# FGPMMOPA6x.net
KiCad netlist of a schematic drawn in EAGLE
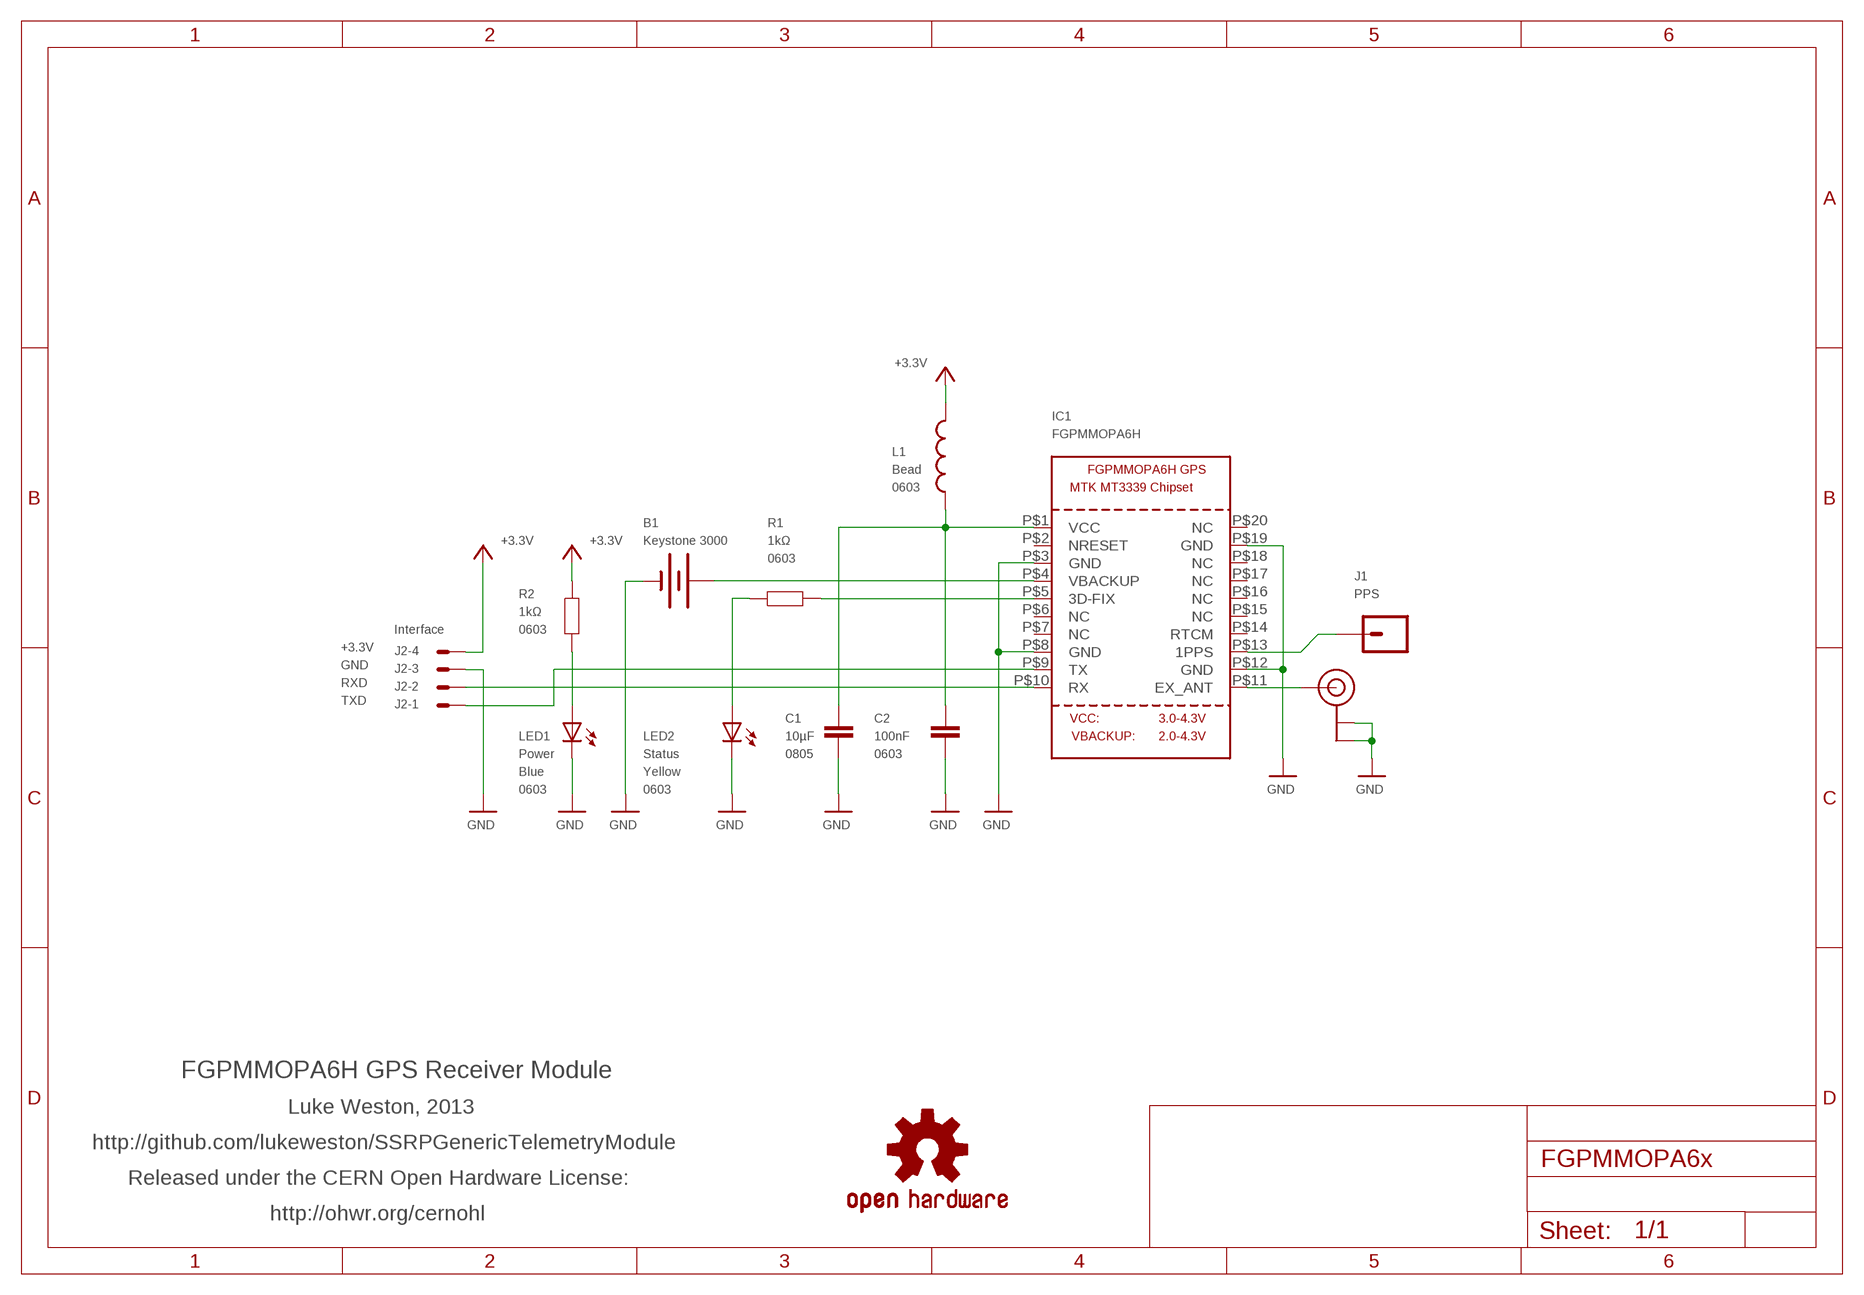
[diagram p0: schematic, sheet 1]

(export (version "E")
  (design (tool "Eeschema 10.0.6"))
  (components
    (comp (ref "B1")
      (value "Keystone 3000")
      (footprint "eagle-import:BATTCON_12MM")
      (libsource (lib "eagle-import") (part "BATTERY12MM"))
    )
    (comp (ref "C1")
      (value "10µF")
      (footprint "eagle-import:0805")
      (fields (field (name "PACKAGE") "0805"))
      (libsource (lib "eagle-import") (part "CAP0805"))
    )
    (comp (ref "C2")
      (value "100nF")
      (footprint "eagle-import:0603")
      (fields (field (name "PACKAGE") "0603"))
      (libsource (lib "eagle-import") (part "CAP0603"))
    )
    (comp (ref "IC1")
      (value "FGPMMOPA6H")
      (footprint "eagle-import:FGPMMOPA6H")
      (libsource (lib "eagle-import") (part "GPS_FGPMMOPA6H"))
    )
    (comp (ref "J1")
      (value "PPS")
      (footprint "eagle-import:1X01")
      (libsource (lib "eagle-import") (part "M01PTH"))
    )
    (comp (ref "J2")
      (value "Interface")
      (footprint "eagle-import:22-23-2041")
      (fields (field (name "MF") "MOLEX") (field (name "MPN") "22-23-2041"))
      (libsource (lib "eagle-import") (part "22-23-2041"))
    )
    (comp (ref "J3")
      (value "U.FL")
      (footprint "eagle-import:U.FL")
      (libsource (lib "eagle-import") (part "U.FL"))
    )
    (comp (ref "L1")
      (value "Bead")
      (footprint "eagle-import:0603")
      (fields (field (name "PACKAGE") "0603"))
      (libsource (lib "eagle-import") (part "INDUCTOR0603"))
    )
    (comp (ref "LED1")
      (value "Power")
      (footprint "eagle-import:LED-0603")
      (fields (field (name "COLOUR") "Blue") (field (name "PACKAGE") "0603"))
      (libsource (lib "eagle-import") (part "LED0603"))
    )
    (comp (ref "LED2")
      (value "Status")
      (footprint "eagle-import:LED-0603")
      (fields (field (name "COLOUR") "Yellow") (field (name "PACKAGE") "0603"))
      (libsource (lib "eagle-import") (part "LED0603"))
    )
    (comp (ref "R1")
      (value "1kΩ")
      (footprint "eagle-import:0603")
      (fields (field (name "PACKAGE") "0603"))
      (libsource (lib "eagle-import") (part "RESISTOR0603"))
    )
    (comp (ref "R2")
      (value "1kΩ")
      (footprint "eagle-import:0603")
      (fields (field (name "PACKAGE") "0603"))
      (libsource (lib "eagle-import") (part "RESISTOR0603"))
    )
    (comp (ref "SY")
      (value "OSHW-LOGOS")
      (footprint "eagle-import:OSHW-LOGO-S")
      (libsource (lib "eagle-import") (part "OSHW-LOGOS"))
    )
  )
  (nets
    (net (code "1") (name "+3.3V") (class "Default")
      (node (ref "J2") (pin "4") (pinfunction "S_4") (pintype "passive"))
      (node (ref "L1") (pin "2") (pinfunction "2_2") (pintype "passive"))
      (node (ref "R2") (pin "2") (pinfunction "2_2") (pintype "passive"))
    )
    (net (code "2") (name "GND") (class "Default")
      (node (ref "B1") (pin "GND") (pinfunction "-_GND") (pintype "power_in"))
      (node (ref "C1") (pin "1") (pinfunction "1_1") (pintype "passive"))
      (node (ref "C2") (pin "1") (pinfunction "1_1") (pintype "passive"))
      (node (ref "IC1") (pin "P$12") (pinfunction "GND_P$12") (pintype "bidirectional"))
      (node (ref "IC1") (pin "P$19") (pinfunction "GND_P$19") (pintype "bidirectional"))
      (node (ref "IC1") (pin "P$3") (pinfunction "GND_P$3") (pintype "bidirectional"))
      (node (ref "IC1") (pin "P$8") (pinfunction "GND_P$8") (pintype "bidirectional"))
      (node (ref "J2") (pin "3") (pinfunction "S_3") (pintype "passive"))
      (node (ref "J3") (pin "P$1") (pinfunction "GND_P$1") (pintype "bidirectional"))
      (node (ref "J3") (pin "P$2") (pinfunction "GND_P$2") (pintype "bidirectional"))
      (node (ref "LED1") (pin "C") (pinfunction "C_C") (pintype "passive"))
      (node (ref "LED2") (pin "C") (pinfunction "C_C") (pintype "passive"))
    )
    (net (code "3") (name "Net-(B1-+)") (class "Default")
      (node (ref "B1") (pin "PWR@1") (pinfunction "+_PWR@1") (pintype "power_in"))
      (node (ref "IC1") (pin "P$4") (pinfunction "VBACKUP_P$4") (pintype "bidirectional"))
    )
    (net (code "4") (name "Net-(IC1-1PPS)") (class "Default")
      (node (ref "IC1") (pin "P$13") (pinfunction "1PPS_P$13") (pintype "bidirectional"))
      (node (ref "J1") (pin "1") (pinfunction "1_1") (pintype "passive"))
    )
    (net (code "5") (name "Net-(IC1-3D-FIX)") (class "Default")
      (node (ref "IC1") (pin "P$5") (pinfunction "3D-FIX_P$5") (pintype "bidirectional"))
      (node (ref "R1") (pin "2") (pinfunction "2_2") (pintype "passive"))
    )
    (net (code "6") (name "Net-(IC1-EX_ANT)") (class "Default")
      (node (ref "IC1") (pin "P$11") (pinfunction "EX_ANT_P$11") (pintype "bidirectional"))
      (node (ref "J3") (pin "P$3") (pinfunction "SIGNAL_P$3") (pintype "bidirectional"))
    )
    (net (code "7") (name "Net-(IC1-RX)") (class "Default")
      (node (ref "IC1") (pin "P$10") (pinfunction "RX_P$10") (pintype "bidirectional"))
      (node (ref "J2") (pin "2") (pinfunction "S_2") (pintype "passive"))
    )
    (net (code "8") (name "Net-(IC1-TX)") (class "Default")
      (node (ref "IC1") (pin "P$9") (pinfunction "TX_P$9") (pintype "bidirectional"))
      (node (ref "J2") (pin "1") (pinfunction "S_1") (pintype "passive"))
    )
    (net (code "9") (name "Net-(IC1-VCC)") (class "Default")
      (node (ref "C1") (pin "2") (pinfunction "2_2") (pintype "passive"))
      (node (ref "C2") (pin "2") (pinfunction "2_2") (pintype "passive"))
      (node (ref "IC1") (pin "P$1") (pinfunction "VCC_P$1") (pintype "bidirectional"))
      (node (ref "L1") (pin "1") (pinfunction "1_1") (pintype "passive"))
    )
    (net (code "10") (name "Net-(LED1-PadA)") (class "Default")
      (node (ref "LED1") (pin "A") (pinfunction "A_A") (pintype "passive"))
      (node (ref "R2") (pin "1") (pinfunction "1_1") (pintype "passive"))
    )
    (net (code "11") (name "Net-(LED2-PadA)") (class "Default")
      (node (ref "LED2") (pin "A") (pinfunction "A_A") (pintype "passive"))
      (node (ref "R1") (pin "1") (pinfunction "1_1") (pintype "passive"))
    )
    (net (code "12") (name "unconnected-(IC1-NC-PadP$6)") (class "Default")
      (node (ref "IC1") (pin "P$6") (pinfunction "NC_P$6") (pintype "bidirectional"))
    )
    (net (code "13") (name "unconnected-(IC1-NC-PadP$7)") (class "Default")
      (node (ref "IC1") (pin "P$7") (pinfunction "NC_P$7") (pintype "bidirectional"))
    )
    (net (code "14") (name "unconnected-(IC1-NC-PadP$15)") (class "Default")
      (node (ref "IC1") (pin "P$15") (pinfunction "NC_P$15") (pintype "bidirectional"))
    )
    (net (code "15") (name "unconnected-(IC1-NC-PadP$16)") (class "Default")
      (node (ref "IC1") (pin "P$16") (pinfunction "NC_P$16") (pintype "bidirectional"))
    )
    (net (code "16") (name "unconnected-(IC1-NC-PadP$17)") (class "Default")
      (node (ref "IC1") (pin "P$17") (pinfunction "NC_P$17") (pintype "bidirectional"))
    )
    (net (code "17") (name "unconnected-(IC1-NC-PadP$18)") (class "Default")
      (node (ref "IC1") (pin "P$18") (pinfunction "NC_P$18") (pintype "bidirectional"))
    )
    (net (code "18") (name "unconnected-(IC1-NC-PadP$20)") (class "Default")
      (node (ref "IC1") (pin "P$20") (pinfunction "NC_P$20") (pintype "bidirectional"))
    )
    (net (code "19") (name "unconnected-(IC1-NRESET-PadP$2)") (class "Default")
      (node (ref "IC1") (pin "P$2") (pinfunction "NRESET_P$2") (pintype "bidirectional"))
    )
    (net (code "20") (name "unconnected-(IC1-RTCM-PadP$14)") (class "Default")
      (node (ref "IC1") (pin "P$14") (pinfunction "RTCM_P$14") (pintype "bidirectional"))
    )
  )
)
